# P2-sematik.net
KiCad netlist of a schematic drawn in Altium Designer
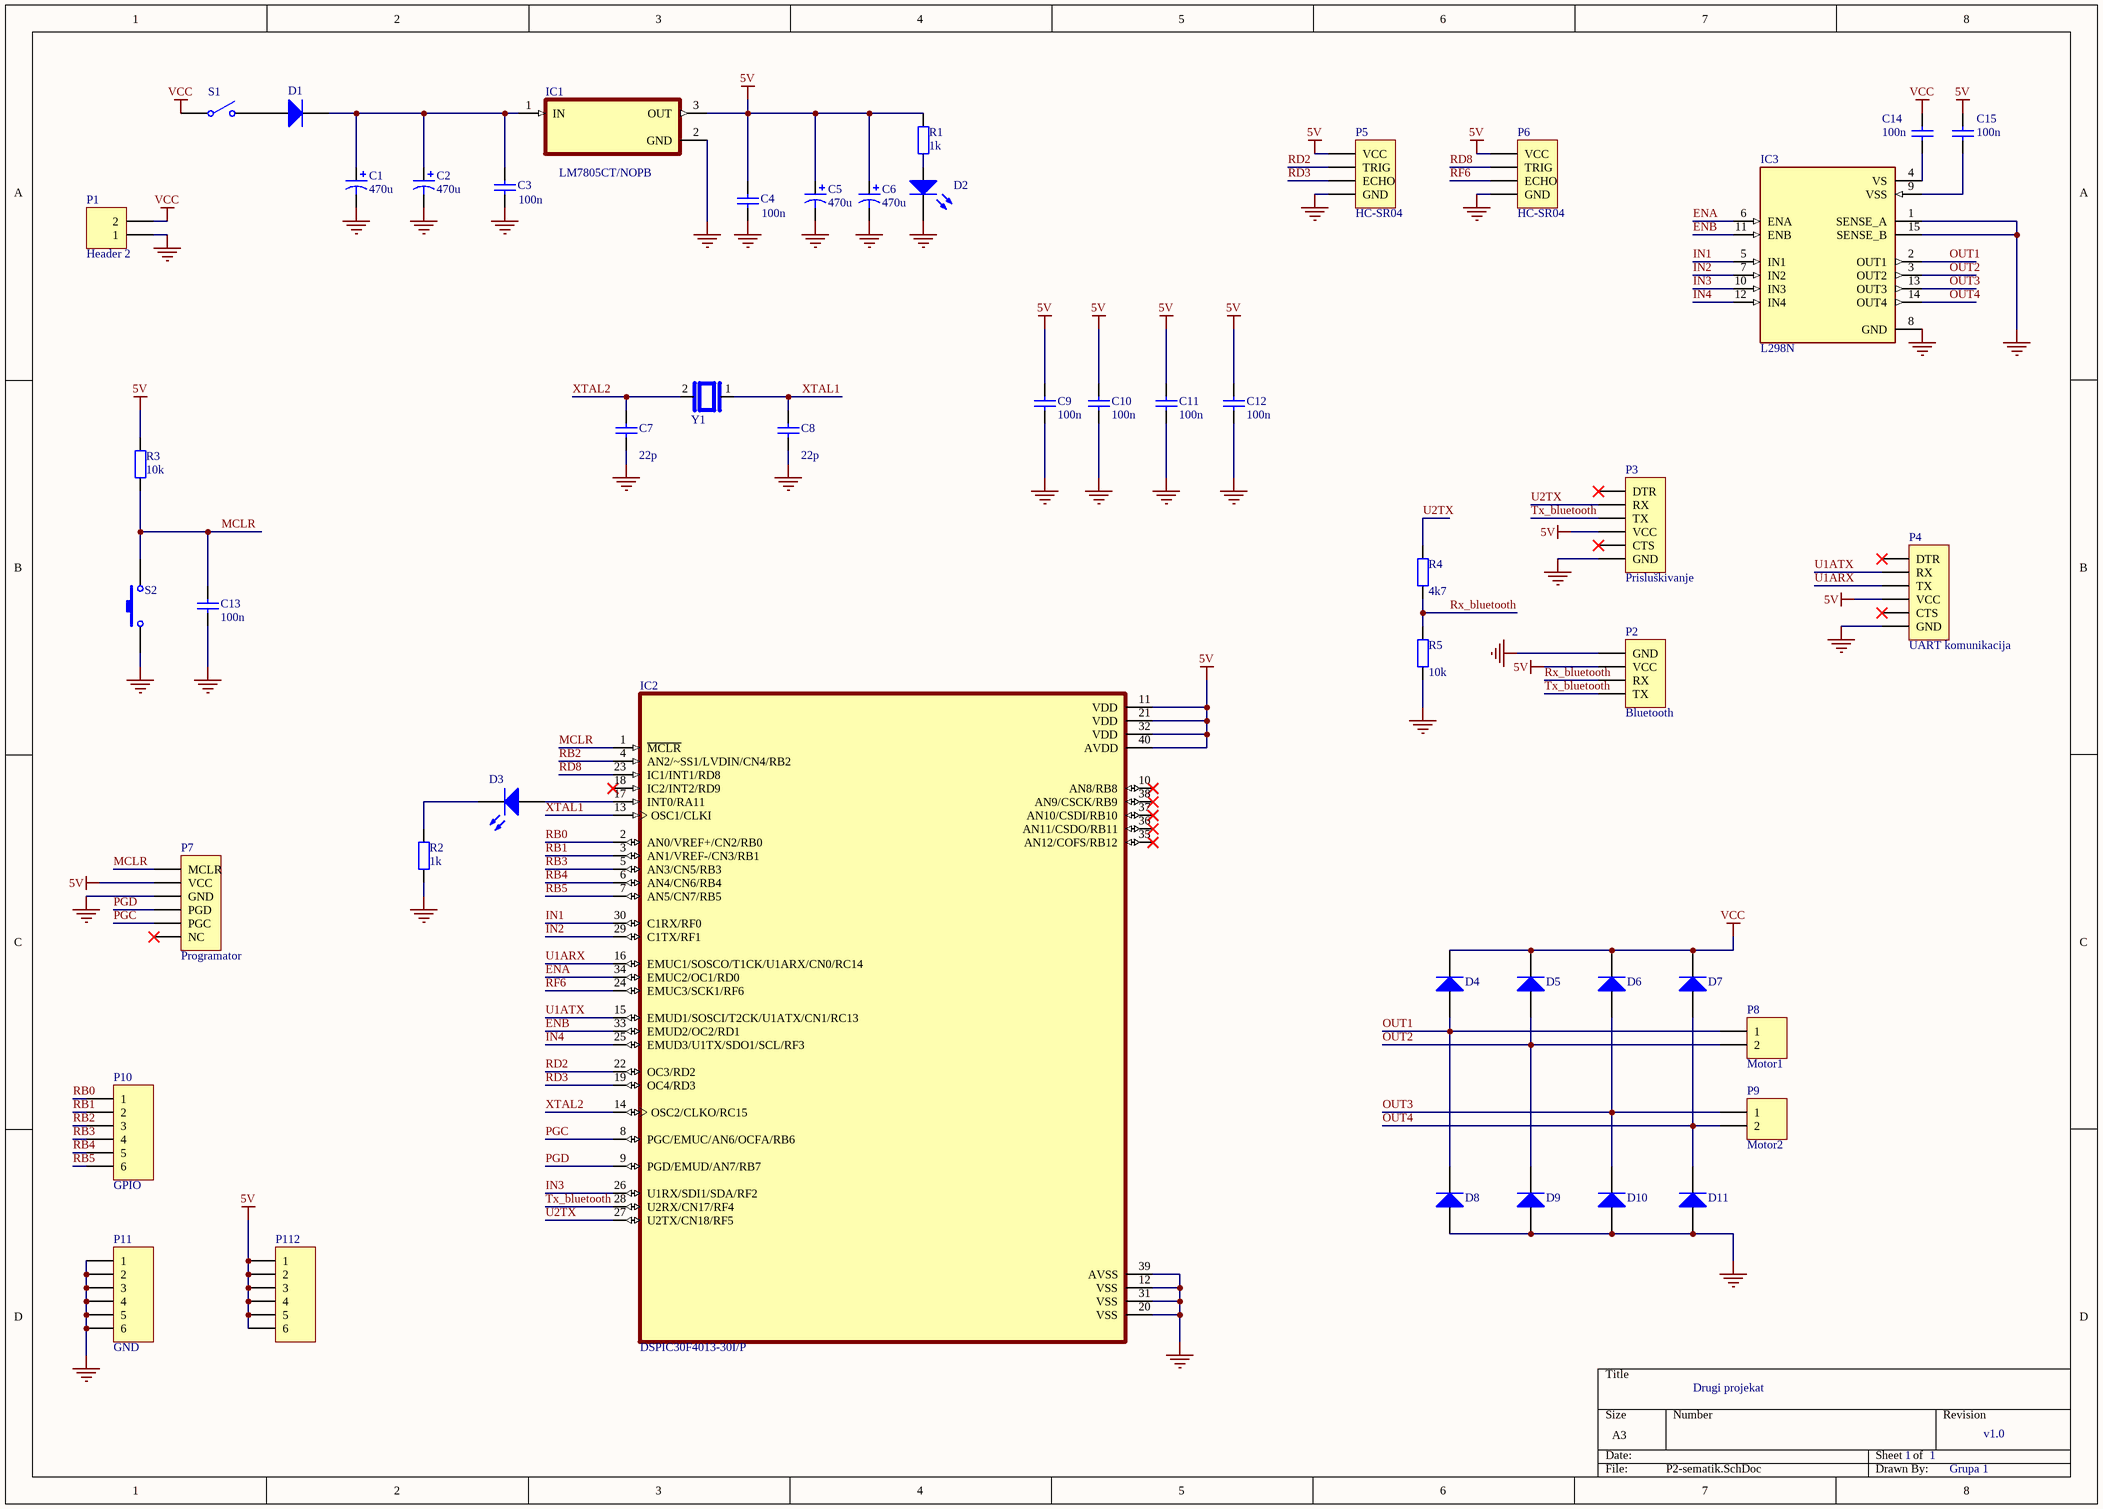
[diagram p0: P2-sematik.SchDoc]

(export (version "E")
  (design (tool "Eeschema 10.0.6"))
  (components
    (comp (ref "C1")
      (value "470u")
      (footprint "elektrolitski kondenzator")
      (description "Polarized Capacitor (Radial)")
      (fields (field (name "Comment") "Cap Pol1") (field (name "PUBLISHER") "Altium Limited"))
      (libsource (lib "Miscellaneous Devices") (part "Cap Pol1"))
    )
    (comp (ref "C2")
      (value "470u")
      (footprint "elektrolitski kondenzator")
      (description "Polarized Capacitor (Radial)")
      (fields (field (name "Comment") "Cap Pol1") (field (name "PUBLISHER") "Altium Limited"))
      (libsource (lib "Miscellaneous Devices") (part "Cap Pol1"))
    )
    (comp (ref "C3")
      (value "100n")
      (footprint "RAD-0.1")
      (description "Capacitor")
      (fields (field (name "Comment") "Cap") (field (name "PUBLISHER") "Altium Limited"))
      (libsource (lib "Miscellaneous Devices") (part "Cap"))
    )
    (comp (ref "C4")
      (value "100n")
      (footprint "RAD-0.1")
      (description "Capacitor")
      (fields (field (name "Comment") "Cap") (field (name "PUBLISHER") "Altium Limited"))
      (libsource (lib "Miscellaneous Devices") (part "Cap"))
    )
    (comp (ref "C5")
      (value "470u")
      (footprint "elektrolitski kondenzator")
      (description "Polarized Capacitor (Radial)")
      (fields (field (name "Comment") "Cap Pol1") (field (name "PUBLISHER") "Altium Limited"))
      (libsource (lib "Miscellaneous Devices") (part "Cap Pol1"))
    )
    (comp (ref "C6")
      (value "470u")
      (footprint "elektrolitski kondenzator")
      (description "Polarized Capacitor (Radial)")
      (fields (field (name "Comment") "Cap Pol1") (field (name "PUBLISHER") "Altium Limited"))
      (libsource (lib "Miscellaneous Devices") (part "Cap Pol1"))
    )
    (comp (ref "C7")
      (value "22p")
      (footprint "RAD-0.2")
      (description "Capacitor")
      (fields (field (name "Comment") "Cap") (field (name "PUBLISHER") "Altium Limited"))
      (libsource (lib "Miscellaneous Devices") (part "Cap"))
    )
    (comp (ref "C8")
      (value "22p")
      (footprint "RAD-0.2")
      (description "Capacitor")
      (fields (field (name "Comment") "Cap") (field (name "PUBLISHER") "Altium Limited"))
      (libsource (lib "Miscellaneous Devices") (part "Cap"))
    )
    (comp (ref "C9")
      (value "100n")
      (footprint "RAD-0.1")
      (description "Capacitor")
      (fields (field (name "Comment") "Cap") (field (name "PUBLISHER") "Altium Limited"))
      (libsource (lib "Miscellaneous Devices") (part "Cap"))
    )
    (comp (ref "C10")
      (value "100n")
      (footprint "RAD-0.1")
      (description "Capacitor")
      (fields (field (name "Comment") "Cap") (field (name "PUBLISHER") "Altium Limited"))
      (libsource (lib "Miscellaneous Devices") (part "Cap"))
    )
    (comp (ref "C11")
      (value "100n")
      (footprint "RAD-0.1")
      (description "Capacitor")
      (fields (field (name "Comment") "Cap") (field (name "PUBLISHER") "Altium Limited"))
      (libsource (lib "Miscellaneous Devices") (part "Cap"))
    )
    (comp (ref "C12")
      (value "100n")
      (footprint "RAD-0.1")
      (description "Capacitor")
      (fields (field (name "Comment") "Cap") (field (name "PUBLISHER") "Altium Limited"))
      (libsource (lib "Miscellaneous Devices") (part "Cap"))
    )
    (comp (ref "C13")
      (value "100n")
      (footprint "RAD-0.1")
      (description "Capacitor")
      (fields (field (name "Comment") "Cap") (field (name "PUBLISHER") "Altium Limited"))
      (libsource (lib "Miscellaneous Devices") (part "Cap"))
    )
    (comp (ref "C14")
      (value "100n")
      (footprint "RAD-0.1")
      (description "Capacitor")
      (fields (field (name "Comment") "Cap") (field (name "PUBLISHER") "Altium Limited"))
      (libsource (lib "Miscellaneous Devices") (part "Cap"))
    )
    (comp (ref "C15")
      (value "100n")
      (footprint "RAD-0.1")
      (description "Capacitor")
      (fields (field (name "Comment") "Cap") (field (name "PUBLISHER") "Altium Limited"))
      (libsource (lib "Miscellaneous Devices") (part "Cap"))
    )
    (comp (ref "D1")
      (value "Diode 1N4007")
      (footprint "DO-41")
      (description "1 Amp General Purpose Rectifier")
      (fields (field (name "PUBLISHER") "Altium Limited"))
      (libsource (lib "Miscellaneous Devices") (part "Diode 1N4007"))
    )
    (comp (ref "D2")
      (value "LED0")
      (footprint "LED dioda")
      (description "Typical INFRARED GaAs LED")
      (fields (field (name "PUBLISHER") "Altium Limited"))
      (libsource (lib "Miscellaneous Devices") (part "LED0"))
    )
    (comp (ref "D3")
      (value "LED0")
      (footprint "LED dioda")
      (description "Typical INFRARED GaAs LED")
      (fields (field (name "PUBLISHER") "Altium Limited"))
      (libsource (lib "Miscellaneous Devices") (part "LED0"))
    )
    (comp (ref "D4")
      (value "Diode 1N4007")
      (footprint "DO-41")
      (description "1 Amp General Purpose Rectifier")
      (fields (field (name "PUBLISHER") "Altium Limited"))
      (libsource (lib "Miscellaneous Devices") (part "Diode 1N4007"))
    )
    (comp (ref "D5")
      (value "Diode 1N4007")
      (footprint "DO-41")
      (description "1 Amp General Purpose Rectifier")
      (fields (field (name "PUBLISHER") "Altium Limited"))
      (libsource (lib "Miscellaneous Devices") (part "Diode 1N4007"))
    )
    (comp (ref "D6")
      (value "Diode 1N4007")
      (footprint "DO-41")
      (description "1 Amp General Purpose Rectifier")
      (fields (field (name "PUBLISHER") "Altium Limited"))
      (libsource (lib "Miscellaneous Devices") (part "Diode 1N4007"))
    )
    (comp (ref "D7")
      (value "Diode 1N4007")
      (footprint "DO-41")
      (description "1 Amp General Purpose Rectifier")
      (fields (field (name "PUBLISHER") "Altium Limited"))
      (libsource (lib "Miscellaneous Devices") (part "Diode 1N4007"))
    )
    (comp (ref "D8")
      (value "Diode 1N4007")
      (footprint "DO-41")
      (description "1 Amp General Purpose Rectifier")
      (fields (field (name "PUBLISHER") "Altium Limited"))
      (libsource (lib "Miscellaneous Devices") (part "Diode 1N4007"))
    )
    (comp (ref "D9")
      (value "Diode 1N4007")
      (footprint "DO-41")
      (description "1 Amp General Purpose Rectifier")
      (fields (field (name "PUBLISHER") "Altium Limited"))
      (libsource (lib "Miscellaneous Devices") (part "Diode 1N4007"))
    )
    (comp (ref "D10")
      (value "Diode 1N4007")
      (footprint "DO-41")
      (description "1 Amp General Purpose Rectifier")
      (fields (field (name "PUBLISHER") "Altium Limited"))
      (libsource (lib "Miscellaneous Devices") (part "Diode 1N4007"))
    )
    (comp (ref "D11")
      (value "Diode 1N4007")
      (footprint "DO-41")
      (description "1 Amp General Purpose Rectifier")
      (fields (field (name "PUBLISHER") "Altium Limited"))
      (libsource (lib "Miscellaneous Devices") (part "Diode 1N4007"))
    )
    (comp (ref "IC1")
      (value "LM7805CT/NOPB")
      (footprint "TO254P1054X470X1955-3")
      (fields (field (name "MF") "{'manufacturer': u'Texas Instruments'}"))
      (libsource (lib "LM7805CT_NOPB") (part "LM7805CT/NOPB"))
    )
    (comp (ref "IC2")
      (value "DSPIC30F4013-30I/P")
      (footprint "Mikrokontroler")
      (description "Digital Signal Processors, DSP, DSC General Purpose ¦ Microchip Technology Inc. DSPIC30F4013-30I/P")
      (fields (field (name "MF") "Microchip"))
      (libsource (lib "DSPIC30F4013-30I_P") (part "DSPIC30F4013-30I/P"))
    )
    (comp (ref "IC3")
      (value "L298N")
      (footprint "TO127P2020X500X2100-15")
      (description "Dual Full Bridge Motor Driver 15-Pin(15+Tab) MULTIWATT V Tube")
      (libsource (lib "L298N") (part "L298N"))
    )
    (comp (ref "P1")
      (value "Header 2")
      (footprint "HDR1X2")
      (description "Header, 2-Pin")
      (fields (field (name "PUBLISHER") "Altium Limited"))
      (libsource (lib "") (part "Header 2_1"))
    )
    (comp (ref "P2")
      (value "Bluetooth")
      (footprint "HDR1X4")
      (description "Header, 4-Pin")
      (fields (field (name "PUBLISHER") "Altium Limited"))
      (libsource (lib "Miscellaneous Connectors") (part "Header 4"))
    )
    (comp (ref "P3")
      (value "Prisluškivanje")
      (footprint "HDR1X6")
      (description "Header, 6-Pin")
      (fields (field (name "PUBLISHER") "Altium Limited"))
      (libsource (lib "Miscellaneous Connectors") (part "Header 6"))
    )
    (comp (ref "P4")
      (value "UART komunikacija")
      (footprint "HDR1X6")
      (description "Header, 6-Pin")
      (fields (field (name "PUBLISHER") "Altium Limited"))
      (libsource (lib "Miscellaneous Connectors") (part "Header 6"))
    )
    (comp (ref "P5")
      (value "HC-SR04")
      (footprint "HDR1X4")
      (description "Header, 4-Pin")
      (fields (field (name "PUBLISHER") "Altium Limited"))
      (libsource (lib "Miscellaneous Connectors") (part "Header 4"))
    )
    (comp (ref "P6")
      (value "HC-SR04")
      (footprint "HDR1X4")
      (description "Header, 4-Pin")
      (fields (field (name "PUBLISHER") "Altium Limited"))
      (libsource (lib "Miscellaneous Connectors") (part "Header 4"))
    )
    (comp (ref "P7")
      (value "Programator")
      (footprint "HDR1X6")
      (description "Header, 6-Pin")
      (fields (field (name "PUBLISHER") "Altium Limited"))
      (libsource (lib "Miscellaneous Connectors") (part "Header 6"))
    )
    (comp (ref "P8")
      (value "Motor1")
      (footprint "HDR1X2")
      (description "Header, 2-Pin")
      (fields (field (name "PUBLISHER") "Altium Limited"))
      (libsource (lib "Miscellaneous Connectors") (part "Header 2"))
    )
    (comp (ref "P9")
      (value "Motor2")
      (footprint "HDR1X2")
      (description "Header, 2-Pin")
      (fields (field (name "PUBLISHER") "Altium Limited"))
      (libsource (lib "Miscellaneous Connectors") (part "Header 2"))
    )
    (comp (ref "P10")
      (value "GPIO")
      (footprint "HDR1X6")
      (description "Header, 6-Pin")
      (fields (field (name "PUBLISHER") "Altium Limited"))
      (libsource (lib "Miscellaneous Connectors") (part "Header 6"))
    )
    (comp (ref "P11")
      (value "GND")
      (footprint "HDR1X6")
      (description "Header, 6-Pin")
      (fields (field (name "PUBLISHER") "Altium Limited"))
      (libsource (lib "Miscellaneous Connectors") (part "Header 6"))
    )
    (comp (ref "P112")
      (value "Header 6")
      (footprint "HDR1X6")
      (description "Header, 6-Pin")
      (fields (field (name "PUBLISHER") "Altium Limited"))
      (libsource (lib "Miscellaneous Connectors") (part "Header 6"))
    )
    (comp (ref "R1")
      (value "1k")
      (footprint "AXIAL-0.3")
      (description "Resistor")
      (fields (field (name "Comment") "Res2") (field (name "PUBLISHER") "Altium Limited"))
      (libsource (lib "") (part "Res2_1"))
    )
    (comp (ref "R2")
      (value "1k")
      (footprint "AXIAL-0.3")
      (description "Resistor")
      (fields (field (name "Comment") "Res2") (field (name "PUBLISHER") "Altium Limited"))
      (libsource (lib "Miscellaneous Devices") (part "Res2"))
    )
    (comp (ref "R3")
      (value "10k")
      (footprint "AXIAL-0.3")
      (description "Resistor")
      (fields (field (name "Comment") "Res2") (field (name "PUBLISHER") "Altium Limited"))
      (libsource (lib "") (part "Res2_1"))
    )
    (comp (ref "R4")
      (value "4k7")
      (footprint "AXIAL-0.3")
      (description "Resistor")
      (fields (field (name "Comment") "Res2") (field (name "PUBLISHER") "Altium Limited"))
      (libsource (lib "") (part "Res2_1"))
    )
    (comp (ref "R5")
      (value "10k")
      (footprint "AXIAL-0.3")
      (description "Resistor")
      (fields (field (name "Comment") "Res2") (field (name "PUBLISHER") "Altium Limited"))
      (libsource (lib "") (part "Res2_1"))
    )
    (comp (ref "S1")
      (value "SW-SPST")
      (footprint "SPST-2")
      (description "Single-Pole, Single-Throw Switch")
      (fields (field (name "PUBLISHER") "Altium Limited"))
      (libsource (lib "Miscellaneous Devices") (part "SW-SPST"))
    )
    (comp (ref "S2")
      (value "SW-PB")
      (footprint "SPST-2")
      (description "Switch")
      (fields (field (name "PUBLISHER") "Altium Limited"))
      (libsource (lib "Miscellaneous Devices") (part "SW-PB"))
    )
    (comp (ref "Y1")
      (value "HC-49/U-S16000000ABJB")
      (footprint "XTAL_HC49P488W43L1150T466H350")
      (description "16 MHz Â±30ppm Crystal 18pF 50 Ohms HC-49/US")
      (fields (field (name "MF") "Citizen Finedevice"))
      (libsource (lib "HC-49_U-S16000000ABJB") (part "HC-49/U-S16000000ABJB"))
    )
  )
  (nets
    (net (code "1") (name "/ENA") (class "Default")
      (node (ref "IC2") (pin "34") (pinfunction "EMUC2/OC1/RD0_34") (pintype "bidirectional"))
      (node (ref "IC3") (pin "6") (pinfunction "ENA_6") (pintype "input"))
    )
    (net (code "2") (name "/ENB") (class "Default")
      (node (ref "IC2") (pin "33") (pinfunction "EMUD2/OC2/RD1_33") (pintype "bidirectional"))
      (node (ref "IC3") (pin "11") (pinfunction "ENB_11") (pintype "input"))
    )
    (net (code "3") (name "/IN1") (class "Default")
      (node (ref "IC2") (pin "30") (pinfunction "C1RX/RF0_30") (pintype "bidirectional"))
      (node (ref "IC3") (pin "5") (pinfunction "IN1_5") (pintype "input"))
    )
    (net (code "4") (name "/IN2") (class "Default")
      (node (ref "IC2") (pin "29") (pinfunction "C1TX/RF1_29") (pintype "bidirectional"))
      (node (ref "IC3") (pin "7") (pinfunction "IN2_7") (pintype "input"))
    )
    (net (code "5") (name "/IN3") (class "Default")
      (node (ref "IC2") (pin "26") (pinfunction "U1RX/SDI1/SDA/RF2_26") (pintype "bidirectional"))
      (node (ref "IC3") (pin "10") (pinfunction "IN3_10") (pintype "input"))
    )
    (net (code "6") (name "/IN4") (class "Default")
      (node (ref "IC2") (pin "25") (pinfunction "EMUD3/U1TX/SDO1/SCL/RF3_25") (pintype "bidirectional"))
      (node (ref "IC3") (pin "12") (pinfunction "IN4_12") (pintype "input"))
    )
    (net (code "7") (name "/MCLR") (class "Default")
      (node (ref "C13") (pin "2") (pinfunction "2_2") (pintype "passive"))
      (node (ref "IC2") (pin "1") (pinfunction "~{MCLR}_1") (pintype "input"))
      (node (ref "P7") (pin "1") (pinfunction "1_1") (pintype "passive"))
      (node (ref "R3") (pin "1") (pinfunction "1_1") (pintype "passive"))
      (node (ref "S2") (pin "2") (pinfunction "2_2") (pintype "passive"))
    )
    (net (code "8") (name "/OUT1") (class "Default")
      (node (ref "D4") (pin "1") (pinfunction "A_1") (pintype "passive"))
      (node (ref "D8") (pin "2") (pinfunction "K_2") (pintype "passive"))
      (node (ref "IC3") (pin "2") (pinfunction "OUT1_2") (pintype "output"))
      (node (ref "P8") (pin "1") (pinfunction "1_1") (pintype "passive"))
    )
    (net (code "9") (name "/OUT2") (class "Default")
      (node (ref "D5") (pin "1") (pinfunction "A_1") (pintype "passive"))
      (node (ref "D9") (pin "2") (pinfunction "K_2") (pintype "passive"))
      (node (ref "IC3") (pin "3") (pinfunction "OUT2_3") (pintype "output"))
      (node (ref "P8") (pin "2") (pinfunction "2_2") (pintype "passive"))
    )
    (net (code "10") (name "/OUT3") (class "Default")
      (node (ref "D10") (pin "2") (pinfunction "K_2") (pintype "passive"))
      (node (ref "D6") (pin "1") (pinfunction "A_1") (pintype "passive"))
      (node (ref "IC3") (pin "13") (pinfunction "OUT3_13") (pintype "output"))
      (node (ref "P9") (pin "1") (pinfunction "1_1") (pintype "passive"))
    )
    (net (code "11") (name "/OUT4") (class "Default")
      (node (ref "D11") (pin "2") (pinfunction "K_2") (pintype "passive"))
      (node (ref "D7") (pin "1") (pinfunction "A_1") (pintype "passive"))
      (node (ref "IC3") (pin "14") (pinfunction "OUT4_14") (pintype "output"))
      (node (ref "P9") (pin "2") (pinfunction "2_2") (pintype "passive"))
    )
    (net (code "12") (name "/PGC") (class "Default")
      (node (ref "IC2") (pin "8") (pinfunction "PGC/EMUC/AN6/OCFA/RB6_8") (pintype "bidirectional"))
      (node (ref "P7") (pin "5") (pinfunction "5_5") (pintype "passive"))
    )
    (net (code "13") (name "/PGD") (class "Default")
      (node (ref "IC2") (pin "9") (pinfunction "PGD/EMUD/AN7/RB7_9") (pintype "bidirectional"))
      (node (ref "P7") (pin "4") (pinfunction "4_4") (pintype "passive"))
    )
    (net (code "14") (name "/RB0") (class "Default")
      (node (ref "IC2") (pin "2") (pinfunction "AN0/VREF+/CN2/RB0_2") (pintype "bidirectional"))
      (node (ref "P10") (pin "1") (pinfunction "1_1") (pintype "passive"))
    )
    (net (code "15") (name "/RB1") (class "Default")
      (node (ref "IC2") (pin "3") (pinfunction "AN1/VREF-/CN3/RB1_3") (pintype "bidirectional"))
      (node (ref "P10") (pin "2") (pinfunction "2_2") (pintype "passive"))
    )
    (net (code "16") (name "/RB2") (class "Default")
      (node (ref "IC2") (pin "4") (pinfunction "AN2/~SS1/LVDIN/CN4/RB2_4") (pintype "input"))
      (node (ref "P10") (pin "3") (pinfunction "3_3") (pintype "passive"))
    )
    (net (code "17") (name "/RB3") (class "Default")
      (node (ref "IC2") (pin "5") (pinfunction "AN3/CN5/RB3_5") (pintype "bidirectional"))
      (node (ref "P10") (pin "4") (pinfunction "4_4") (pintype "passive"))
    )
    (net (code "18") (name "/RB4") (class "Default")
      (node (ref "IC2") (pin "6") (pinfunction "AN4/CN6/RB4_6") (pintype "bidirectional"))
      (node (ref "P10") (pin "5") (pinfunction "5_5") (pintype "passive"))
    )
    (net (code "19") (name "/RB5") (class "Default")
      (node (ref "IC2") (pin "7") (pinfunction "AN5/CN7/RB5_7") (pintype "bidirectional"))
      (node (ref "P10") (pin "6") (pinfunction "6_6") (pintype "passive"))
    )
    (net (code "20") (name "/RD2") (class "Default")
      (node (ref "IC2") (pin "22") (pinfunction "OC3/RD2_22") (pintype "bidirectional"))
      (node (ref "P5") (pin "2") (pinfunction "TRIG_2") (pintype "passive"))
    )
    (net (code "21") (name "/RD3") (class "Default")
      (node (ref "IC2") (pin "19") (pinfunction "OC4/RD3_19") (pintype "bidirectional"))
      (node (ref "P5") (pin "3") (pinfunction "ECHO_3") (pintype "passive"))
    )
    (net (code "22") (name "/RD8") (class "Default")
      (node (ref "IC2") (pin "23") (pinfunction "IC1/INT1/RD8_23") (pintype "input"))
      (node (ref "P6") (pin "2") (pinfunction "TRIG_2") (pintype "passive"))
    )
    (net (code "23") (name "/RF6") (class "Default")
      (node (ref "IC2") (pin "24") (pinfunction "EMUC3/SCK1/RF6_24") (pintype "bidirectional"))
      (node (ref "P6") (pin "3") (pinfunction "ECHO_3") (pintype "passive"))
    )
    (net (code "24") (name "/Rx_bluetooth") (class "Default")
      (node (ref "P2") (pin "3") (pinfunction "ECHO_3") (pintype "passive"))
      (node (ref "R4") (pin "1") (pinfunction "1_1") (pintype "passive"))
      (node (ref "R5") (pin "2") (pinfunction "2_2") (pintype "passive"))
    )
    (net (code "25") (name "/Tx_bluetooth") (class "Default")
      (node (ref "IC2") (pin "28") (pinfunction "U2RX/CN17/RF4_28") (pintype "bidirectional"))
      (node (ref "P2") (pin "4") (pinfunction "GND_4") (pintype "passive"))
      (node (ref "P3") (pin "3") (pinfunction "3_3") (pintype "passive"))
    )
    (net (code "26") (name "/U1ARX") (class "Default")
      (node (ref "IC2") (pin "16") (pinfunction "EMUC1/SOSCO/T1CK/U1ARX/CN0/RC14_16") (pintype "bidirectional"))
      (node (ref "P4") (pin "3") (pinfunction "3_3") (pintype "passive"))
    )
    (net (code "27") (name "/U1ATX") (class "Default")
      (node (ref "IC2") (pin "15") (pinfunction "EMUD1/SOSCI/T2CK/U1ATX/CN1/RC13_15") (pintype "bidirectional"))
      (node (ref "P4") (pin "2") (pinfunction "2_2") (pintype "passive"))
    )
    (net (code "28") (name "/U2TX") (class "Default")
      (node (ref "IC2") (pin "27") (pinfunction "U2TX/CN18/RF5_27") (pintype "bidirectional"))
      (node (ref "P3") (pin "2") (pinfunction "2_2") (pintype "passive"))
      (node (ref "R4") (pin "2") (pinfunction "2_2") (pintype "passive"))
    )
    (net (code "29") (name "/XTAL1") (class "Default")
      (node (ref "C8") (pin "2") (pinfunction "2_2") (pintype "passive"))
      (node (ref "IC2") (pin "13") (pinfunction "OSC1/CLKI_13") (pintype "input"))
      (node (ref "Y1") (pin "1") (pinfunction "1_1") (pintype "passive"))
    )
    (net (code "30") (name "/XTAL2") (class "Default")
      (node (ref "C7") (pin "2") (pinfunction "2_2") (pintype "passive"))
      (node (ref "IC2") (pin "14") (pinfunction "OSC2/CLKO/RC15_14") (pintype "bidirectional"))
      (node (ref "Y1") (pin "2") (pinfunction "2_2") (pintype "passive"))
    )
    (net (code "31") (name "5V") (class "Default")
      (node (ref "C10") (pin "1") (pinfunction "1_1") (pintype "passive"))
      (node (ref "C11") (pin "1") (pinfunction "1_1") (pintype "passive"))
      (node (ref "C12") (pin "1") (pinfunction "1_1") (pintype "passive"))
      (node (ref "C15") (pin "2") (pinfunction "2_2") (pintype "passive"))
      (node (ref "C4") (pin "2") (pinfunction "2_2") (pintype "passive"))
      (node (ref "C5") (pin "1") (pinfunction "1_1") (pintype "passive"))
      (node (ref "C6") (pin "1") (pinfunction "1_1") (pintype "passive"))
      (node (ref "C9") (pin "1") (pinfunction "1_1") (pintype "passive"))
      (node (ref "IC1") (pin "3") (pinfunction "OUT_3") (pintype "output"))
      (node (ref "IC2") (pin "11") (pinfunction "VDD_11") (pintype "power_in"))
      (node (ref "IC2") (pin "21") (pinfunction "VDD_21") (pintype "power_in"))
      (node (ref "IC2") (pin "32") (pinfunction "VDD_32") (pintype "power_in"))
      (node (ref "IC2") (pin "40") (pinfunction "AVDD_40") (pintype "power_in"))
      (node (ref "P112") (pin "1") (pinfunction "1_1") (pintype "passive"))
      (node (ref "P112") (pin "2") (pinfunction "2_2") (pintype "passive"))
      (node (ref "P112") (pin "3") (pinfunction "3_3") (pintype "passive"))
      (node (ref "P112") (pin "4") (pinfunction "4_4") (pintype "passive"))
      (node (ref "P112") (pin "5") (pinfunction "5_5") (pintype "passive"))
      (node (ref "P112") (pin "6") (pinfunction "6_6") (pintype "passive"))
      (node (ref "P2") (pin "2") (pinfunction "TRIG_2") (pintype "passive"))
      (node (ref "P3") (pin "4") (pinfunction "4_4") (pintype "passive"))
      (node (ref "P4") (pin "4") (pinfunction "4_4") (pintype "passive"))
      (node (ref "P5") (pin "1") (pinfunction "VCC_1") (pintype "passive"))
      (node (ref "P6") (pin "1") (pinfunction "VCC_1") (pintype "passive"))
      (node (ref "P7") (pin "2") (pinfunction "2_2") (pintype "passive"))
      (node (ref "R1") (pin "2") (pinfunction "2_2") (pintype "passive"))
      (node (ref "R3") (pin "2") (pinfunction "2_2") (pintype "passive"))
    )
    (net (code "32") (name "GND") (class "Default")
      (node (ref "C1") (pin "2") (pinfunction "2_2") (pintype "passive"))
      (node (ref "C10") (pin "2") (pinfunction "2_2") (pintype "passive"))
      (node (ref "C11") (pin "2") (pinfunction "2_2") (pintype "passive"))
      (node (ref "C12") (pin "2") (pinfunction "2_2") (pintype "passive"))
      (node (ref "C13") (pin "1") (pinfunction "1_1") (pintype "passive"))
      (node (ref "C2") (pin "2") (pinfunction "2_2") (pintype "passive"))
      (node (ref "C3") (pin "1") (pinfunction "1_1") (pintype "passive"))
      (node (ref "C4") (pin "1") (pinfunction "1_1") (pintype "passive"))
      (node (ref "C5") (pin "2") (pinfunction "2_2") (pintype "passive"))
      (node (ref "C6") (pin "2") (pinfunction "2_2") (pintype "passive"))
      (node (ref "C7") (pin "1") (pinfunction "1_1") (pintype "passive"))
      (node (ref "C8") (pin "1") (pinfunction "1_1") (pintype "passive"))
      (node (ref "C9") (pin "2") (pinfunction "2_2") (pintype "passive"))
      (node (ref "D10") (pin "1") (pinfunction "A_1") (pintype "passive"))
      (node (ref "D11") (pin "1") (pinfunction "A_1") (pintype "passive"))
      (node (ref "D2") (pin "2") (pinfunction "K_2") (pintype "passive"))
      (node (ref "D8") (pin "1") (pinfunction "A_1") (pintype "passive"))
      (node (ref "D9") (pin "1") (pinfunction "A_1") (pintype "passive"))
      (node (ref "IC1") (pin "2") (pinfunction "GND_2") (pintype "power_in"))
      (node (ref "IC2") (pin "12") (pinfunction "VSS_12") (pintype "power_in"))
      (node (ref "IC2") (pin "20") (pinfunction "VSS_20") (pintype "power_in"))
      (node (ref "IC2") (pin "31") (pinfunction "VSS_31") (pintype "power_in"))
      (node (ref "IC2") (pin "39") (pinfunction "AVSS_39") (pintype "power_in"))
      (node (ref "IC3") (pin "1") (pinfunction "SENSE_A_1") (pintype "passive"))
      (node (ref "IC3") (pin "15") (pinfunction "SENSE_B_15") (pintype "passive"))
      (node (ref "IC3") (pin "8") (pinfunction "GND_8") (pintype "power_in"))
      (node (ref "P1") (pin "1") (pinfunction "1_1") (pintype "passive"))
      (node (ref "P11") (pin "1") (pinfunction "1_1") (pintype "passive"))
      (node (ref "P11") (pin "2") (pinfunction "2_2") (pintype "passive"))
      (node (ref "P11") (pin "3") (pinfunction "3_3") (pintype "passive"))
      (node (ref "P11") (pin "4") (pinfunction "4_4") (pintype "passive"))
      (node (ref "P11") (pin "5") (pinfunction "5_5") (pintype "passive"))
      (node (ref "P11") (pin "6") (pinfunction "6_6") (pintype "passive"))
      (node (ref "P2") (pin "1") (pinfunction "VCC_1") (pintype "passive"))
      (node (ref "P3") (pin "6") (pinfunction "6_6") (pintype "passive"))
      (node (ref "P4") (pin "6") (pinfunction "6_6") (pintype "passive"))
      (node (ref "P5") (pin "4") (pinfunction "GND_4") (pintype "passive"))
      (node (ref "P6") (pin "4") (pinfunction "GND_4") (pintype "passive"))
      (node (ref "P7") (pin "3") (pinfunction "3_3") (pintype "passive"))
      (node (ref "R2") (pin "2") (pinfunction "2_2") (pintype "passive"))
      (node (ref "R5") (pin "1") (pinfunction "1_1") (pintype "passive"))
      (node (ref "S2") (pin "1") (pinfunction "1_1") (pintype "passive"))
    )
    (net (code "33") (name "Net-(D1-A)") (class "Default")
      (node (ref "D1") (pin "1") (pinfunction "A_1") (pintype "passive"))
      (node (ref "S1") (pin "2") (pinfunction "NO_2") (pintype "passive"))
    )
    (net (code "34") (name "Net-(D1-K)") (class "Default")
      (node (ref "C1") (pin "1") (pinfunction "1_1") (pintype "passive"))
      (node (ref "C2") (pin "1") (pinfunction "1_1") (pintype "passive"))
      (node (ref "C3") (pin "2") (pinfunction "2_2") (pintype "passive"))
      (node (ref "D1") (pin "2") (pinfunction "K_2") (pintype "passive"))
      (node (ref "IC1") (pin "1") (pinfunction "IN_1") (pintype "input"))
    )
    (net (code "35") (name "Net-(D2-A)") (class "Default")
      (node (ref "D2") (pin "1") (pinfunction "A_1") (pintype "passive"))
      (node (ref "R1") (pin "1") (pinfunction "1_1") (pintype "passive"))
    )
    (net (code "36") (name "Net-(D3-A)") (class "Default")
      (node (ref "D3") (pin "1") (pinfunction "A_1") (pintype "passive"))
      (node (ref "IC2") (pin "17") (pinfunction "INT0/RA11_17") (pintype "input"))
    )
    (net (code "37") (name "Net-(D3-K)") (class "Default")
      (node (ref "D3") (pin "2") (pinfunction "K_2") (pintype "passive"))
      (node (ref "R2") (pin "1") (pinfunction "1_1") (pintype "passive"))
    )
    (net (code "38") (name "Net-(IC3-VS)") (class "Default")
      (node (ref "C14") (pin "1") (pinfunction "1_1") (pintype "passive"))
      (node (ref "IC3") (pin "4") (pinfunction "VS_4") (pintype "power_in"))
    )
    (net (code "39") (name "Net-(IC3-VSS)") (class "Default")
      (node (ref "C15") (pin "1") (pinfunction "1_1") (pintype "passive"))
      (node (ref "IC3") (pin "9") (pinfunction "VSS_9") (pintype "input"))
    )
    (net (code "40") (name "VCC") (class "Default")
      (node (ref "C14") (pin "2") (pinfunction "2_2") (pintype "passive"))
      (node (ref "D4") (pin "2") (pinfunction "K_2") (pintype "passive"))
      (node (ref "D5") (pin "2") (pinfunction "K_2") (pintype "passive"))
      (node (ref "D6") (pin "2") (pinfunction "K_2") (pintype "passive"))
      (node (ref "D7") (pin "2") (pinfunction "K_2") (pintype "passive"))
      (node (ref "P1") (pin "2") (pinfunction "2_2") (pintype "passive"))
      (node (ref "S1") (pin "1") (pinfunction "COMMON_1") (pintype "passive"))
    )
    (net (code "41") (name "unconnected-(IC2-AN8{slash}RB8-Pad10)") (class "Default")
      (node (ref "IC2") (pin "10") (pinfunction "AN8/RB8_10") (pintype "bidirectional+no_connect"))
    )
    (net (code "42") (name "unconnected-(IC2-AN9{slash}CSCK{slash}RB9-Pad38)") (class "Default")
      (node (ref "IC2") (pin "38") (pinfunction "AN9/CSCK/RB9_38") (pintype "bidirectional+no_connect"))
    )
    (net (code "43") (name "unconnected-(IC2-AN10{slash}CSDI{slash}RB10-Pad37)") (class "Default")
      (node (ref "IC2") (pin "37") (pinfunction "AN10/CSDI/RB10_37") (pintype "bidirectional+no_connect"))
    )
    (net (code "44") (name "unconnected-(IC2-AN11{slash}CSDO{slash}RB11-Pad36)") (class "Default")
      (node (ref "IC2") (pin "36") (pinfunction "AN11/CSDO/RB11_36") (pintype "bidirectional+no_connect"))
    )
    (net (code "45") (name "unconnected-(IC2-AN12{slash}COFS{slash}RB12-Pad35)") (class "Default")
      (node (ref "IC2") (pin "35") (pinfunction "AN12/COFS/RB12_35") (pintype "bidirectional+no_connect"))
    )
    (net (code "46") (name "unconnected-(IC2-IC2{slash}INT2{slash}RD9-Pad18)") (class "Default")
      (node (ref "IC2") (pin "18") (pinfunction "IC2/INT2/RD9_18") (pintype "input+no_connect"))
    )
    (net (code "47") (name "unconnected-(P3-Pad1)") (class "Default")
      (node (ref "P3") (pin "1") (pinfunction "1_1") (pintype "passive+no_connect"))
    )
    (net (code "48") (name "unconnected-(P3-Pad5)") (class "Default")
      (node (ref "P3") (pin "5") (pinfunction "5_5") (pintype "passive+no_connect"))
    )
    (net (code "49") (name "unconnected-(P4-Pad1)") (class "Default")
      (node (ref "P4") (pin "1") (pinfunction "1_1") (pintype "passive+no_connect"))
    )
    (net (code "50") (name "unconnected-(P4-Pad5)") (class "Default")
      (node (ref "P4") (pin "5") (pinfunction "5_5") (pintype "passive+no_connect"))
    )
    (net (code "51") (name "unconnected-(P7-Pad6)") (class "Default")
      (node (ref "P7") (pin "6") (pinfunction "6_6") (pintype "passive+no_connect"))
    )
  )
)
